# LightingBoard2.net
KiCad netlist of a schematic drawn in EAGLE
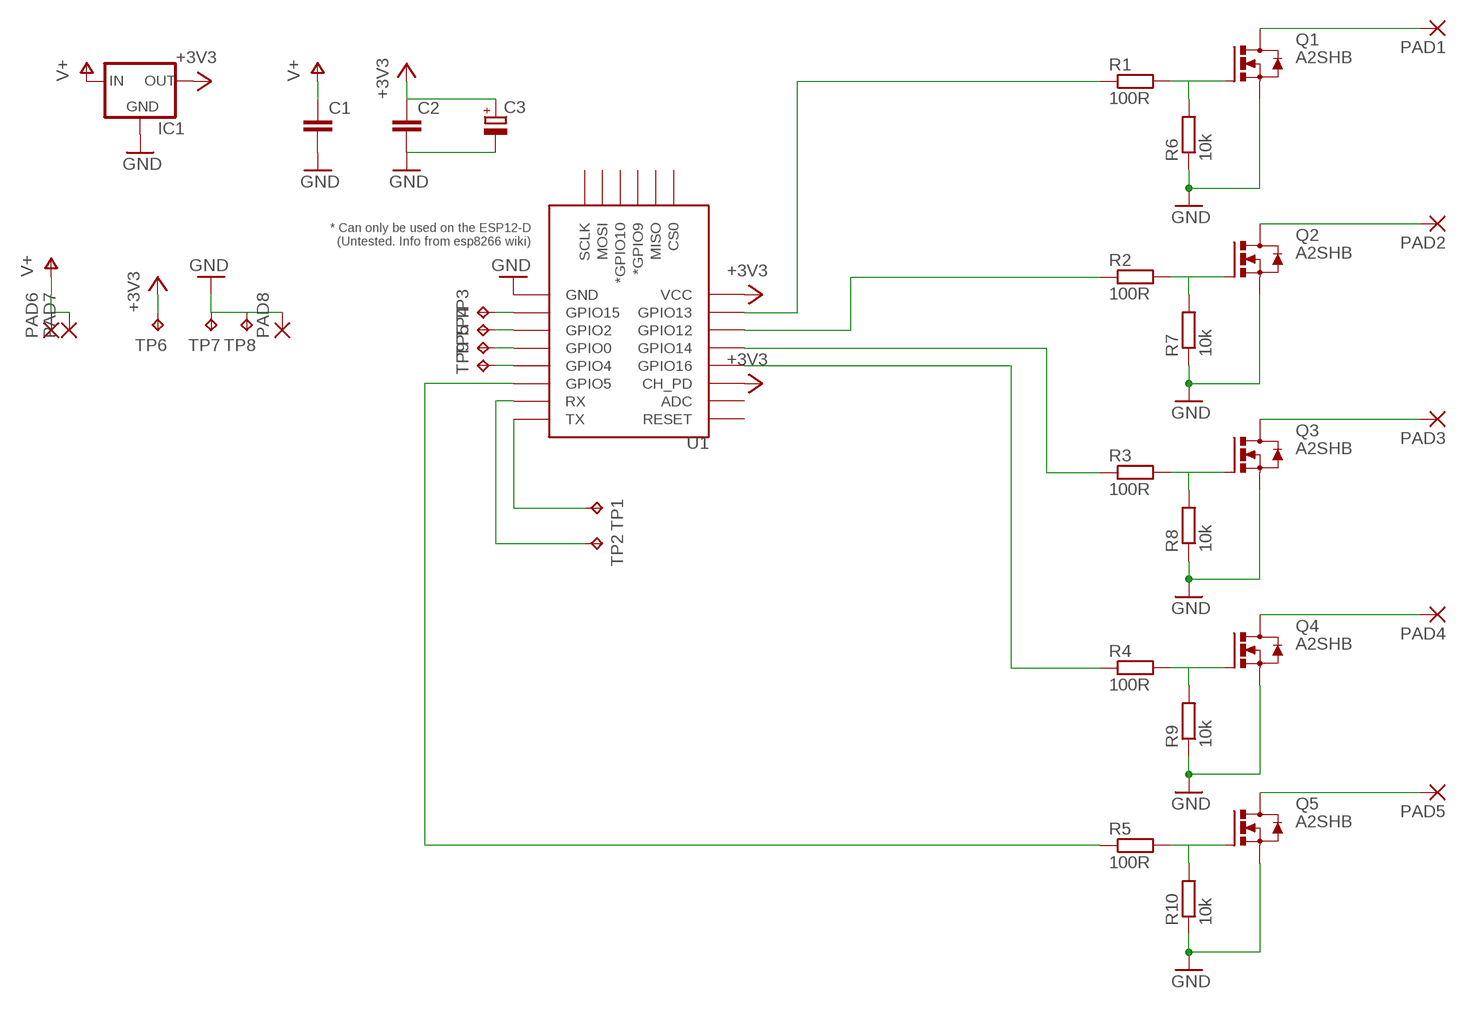
[diagram p0: schematic, sheet 1]

(export (version "E")
  (design (tool "Eeschema 10.0.6"))
  (components
    (comp (ref "C1")
      (value "C-EUC0603")
      (footprint "eagle-import:C0603")
      (libsource (lib "eagle-import") (part "C-EUC0603"))
    )
    (comp (ref "C2")
      (value "C-EUC0603")
      (footprint "eagle-import:C0603")
      (libsource (lib "eagle-import") (part "C-EUC0603"))
    )
    (comp (ref "C3")
      (value "CPOL-EU153CLV-0505")
      (footprint "eagle-import:153CLV-0505")
      (libsource (lib "eagle-import") (part "CPOL-EU153CLV-0505"))
    )
    (comp (ref "IC1")
      (value "LM1117")
      (footprint "eagle-import:SOT223")
      (libsource (lib "eagle-import") (part "LM1117"))
    )
    (comp (ref "PAD1")
      (value "SMD5")
      (footprint "eagle-import:SMD2,54-5,08")
      (libsource (lib "eagle-import") (part "SMD5"))
    )
    (comp (ref "PAD2")
      (value "SMD5")
      (footprint "eagle-import:SMD2,54-5,08")
      (libsource (lib "eagle-import") (part "SMD5"))
    )
    (comp (ref "PAD3")
      (value "SMD5")
      (footprint "eagle-import:SMD2,54-5,08")
      (libsource (lib "eagle-import") (part "SMD5"))
    )
    (comp (ref "PAD4")
      (value "SMD5")
      (footprint "eagle-import:SMD2,54-5,08")
      (libsource (lib "eagle-import") (part "SMD5"))
    )
    (comp (ref "PAD5")
      (value "SMD5")
      (footprint "eagle-import:SMD2,54-5,08")
      (libsource (lib "eagle-import") (part "SMD5"))
    )
    (comp (ref "PAD6")
      (value "SMD5")
      (footprint "eagle-import:SMD2,54-5,08")
      (libsource (lib "eagle-import") (part "SMD5"))
    )
    (comp (ref "PAD7")
      (value "SMD5")
      (footprint "eagle-import:SMD2,54-5,08")
      (libsource (lib "eagle-import") (part "SMD5"))
    )
    (comp (ref "PAD8")
      (value "SMD5")
      (footprint "eagle-import:SMD2,54-5,08")
      (libsource (lib "eagle-import") (part "SMD5"))
    )
    (comp (ref "Q1")
      (value "A2SHB")
      (footprint "eagle-import:SOT23")
      (libsource (lib "eagle-import") (part "MOSFET_N_SOT231"))
    )
    (comp (ref "Q2")
      (value "A2SHB")
      (footprint "eagle-import:SOT23")
      (libsource (lib "eagle-import") (part "MOSFET_N_SOT231"))
    )
    (comp (ref "Q3")
      (value "A2SHB")
      (footprint "eagle-import:SOT23")
      (libsource (lib "eagle-import") (part "MOSFET_N_SOT231"))
    )
    (comp (ref "Q4")
      (value "A2SHB")
      (footprint "eagle-import:SOT23")
      (libsource (lib "eagle-import") (part "MOSFET_N_SOT231"))
    )
    (comp (ref "Q5")
      (value "A2SHB")
      (footprint "eagle-import:SOT23")
      (libsource (lib "eagle-import") (part "MOSFET_N_SOT231"))
    )
    (comp (ref "R1")
      (value "100R")
      (footprint "eagle-import:R0603")
      (libsource (lib "eagle-import") (part "R-EU_R0603"))
    )
    (comp (ref "R2")
      (value "100R")
      (footprint "eagle-import:R0603")
      (libsource (lib "eagle-import") (part "R-EU_R0603"))
    )
    (comp (ref "R3")
      (value "100R")
      (footprint "eagle-import:R0603")
      (libsource (lib "eagle-import") (part "R-EU_R0603"))
    )
    (comp (ref "R4")
      (value "100R")
      (footprint "eagle-import:R0603")
      (libsource (lib "eagle-import") (part "R-EU_R0603"))
    )
    (comp (ref "R5")
      (value "100R")
      (footprint "eagle-import:R0603")
      (libsource (lib "eagle-import") (part "R-EU_R0603"))
    )
    (comp (ref "R6")
      (value "10k")
      (footprint "eagle-import:R0603")
      (libsource (lib "eagle-import") (part "R-EU_R0603"))
    )
    (comp (ref "R7")
      (value "10k")
      (footprint "eagle-import:R0603")
      (libsource (lib "eagle-import") (part "R-EU_R0603"))
    )
    (comp (ref "R8")
      (value "10k")
      (footprint "eagle-import:R0603")
      (libsource (lib "eagle-import") (part "R-EU_R0603"))
    )
    (comp (ref "R9")
      (value "10k")
      (footprint "eagle-import:R0603")
      (libsource (lib "eagle-import") (part "R-EU_R0603"))
    )
    (comp (ref "R10")
      (value "10k")
      (footprint "eagle-import:R0603")
      (libsource (lib "eagle-import") (part "R-EU_R0603"))
    )
    (comp (ref "TP1")
      (value "TPTP18R")
      (footprint "eagle-import:TP18R")
      (libsource (lib "eagle-import") (part "TPTP18R"))
    )
    (comp (ref "TP2")
      (value "TPTP18R")
      (footprint "eagle-import:TP18R")
      (libsource (lib "eagle-import") (part "TPTP18R"))
    )
    (comp (ref "TP3")
      (value "TPTP12SQ")
      (footprint "eagle-import:TP12SQ")
      (libsource (lib "eagle-import") (part "TPTP12SQ"))
    )
    (comp (ref "TP4")
      (value "TPTP12SQ")
      (footprint "eagle-import:TP12SQ")
      (libsource (lib "eagle-import") (part "TPTP12SQ"))
    )
    (comp (ref "TP5")
      (value "TPTP12SQ")
      (footprint "eagle-import:TP12SQ")
      (libsource (lib "eagle-import") (part "TPTP12SQ"))
    )
    (comp (ref "TP6")
      (value "TPTP12SQ")
      (footprint "eagle-import:TP12SQ")
      (libsource (lib "eagle-import") (part "TPTP12SQ"))
    )
    (comp (ref "TP7")
      (value "TPTP12SQ")
      (footprint "eagle-import:TP12SQ")
      (libsource (lib "eagle-import") (part "TPTP12SQ"))
    )
    (comp (ref "TP8")
      (value "TPTP12SQ")
      (footprint "eagle-import:TP12SQ")
      (libsource (lib "eagle-import") (part "TPTP12SQ"))
    )
    (comp (ref "TP9")
      (value "TPTP12SQ")
      (footprint "eagle-import:TP12SQ")
      (libsource (lib "eagle-import") (part "TPTP12SQ"))
    )
    (comp (ref "U1")
      (value "ESP12ESMD")
      (footprint "eagle-import:ESP12E-SMD")
      (libsource (lib "eagle-import") (part "ESP12ESMD"))
    )
  )
  (nets
    (net (code "1") (name "+3V3") (class "Default")
      (node (ref "C2") (pin "1") (pinfunction "1_1") (pintype "passive"))
      (node (ref "C3") (pin "+") (pinfunction "+_+") (pintype "passive"))
      (node (ref "IC1") (pin "2") (pinfunction "OUT_2") (pintype "passive"))
      (node (ref "TP6") (pin "TP") (pinfunction "TP_TP") (pintype "input"))
      (node (ref "U1") (pin "CH_PD") (pinfunction "CH_PD_CH_PD") (pintype "bidirectional"))
      (node (ref "U1") (pin "VCC") (pinfunction "VCC_VCC") (pintype "bidirectional"))
    )
    (net (code "2") (name "GND") (class "Default")
      (node (ref "C1") (pin "2") (pinfunction "2_2") (pintype "passive"))
      (node (ref "C2") (pin "2") (pinfunction "2_2") (pintype "passive"))
      (node (ref "C3") (pin "-") (pinfunction "-_-") (pintype "passive"))
      (node (ref "IC1") (pin "1") (pinfunction "GND_1") (pintype "input"))
      (node (ref "PAD8") (pin "1") (pinfunction "P_1") (pintype "passive"))
      (node (ref "Q1") (pin "2") (pinfunction "S_2") (pintype "passive"))
      (node (ref "Q2") (pin "2") (pinfunction "S_2") (pintype "passive"))
      (node (ref "Q3") (pin "2") (pinfunction "S_2") (pintype "passive"))
      (node (ref "Q4") (pin "2") (pinfunction "S_2") (pintype "passive"))
      (node (ref "Q5") (pin "2") (pinfunction "S_2") (pintype "passive"))
      (node (ref "R10") (pin "1") (pinfunction "1_1") (pintype "passive"))
      (node (ref "R6") (pin "1") (pinfunction "1_1") (pintype "passive"))
      (node (ref "R7") (pin "1") (pinfunction "1_1") (pintype "passive"))
      (node (ref "R8") (pin "1") (pinfunction "1_1") (pintype "passive"))
      (node (ref "R9") (pin "1") (pinfunction "1_1") (pintype "passive"))
      (node (ref "TP7") (pin "TP") (pinfunction "TP_TP") (pintype "input"))
      (node (ref "TP8") (pin "TP") (pinfunction "TP_TP") (pintype "input"))
      (node (ref "U1") (pin "GND") (pinfunction "GND_GND") (pintype "bidirectional"))
    )
    (net (code "3") (name "Net-(PAD1-P)") (class "Default")
      (node (ref "PAD1") (pin "1") (pinfunction "P_1") (pintype "passive"))
      (node (ref "Q1") (pin "3") (pinfunction "D_3") (pintype "passive"))
    )
    (net (code "4") (name "Net-(PAD2-P)") (class "Default")
      (node (ref "PAD2") (pin "1") (pinfunction "P_1") (pintype "passive"))
      (node (ref "Q2") (pin "3") (pinfunction "D_3") (pintype "passive"))
    )
    (net (code "5") (name "Net-(PAD3-P)") (class "Default")
      (node (ref "PAD3") (pin "1") (pinfunction "P_1") (pintype "passive"))
      (node (ref "Q3") (pin "3") (pinfunction "D_3") (pintype "passive"))
    )
    (net (code "6") (name "Net-(PAD4-P)") (class "Default")
      (node (ref "PAD4") (pin "1") (pinfunction "P_1") (pintype "passive"))
      (node (ref "Q4") (pin "3") (pinfunction "D_3") (pintype "passive"))
    )
    (net (code "7") (name "Net-(PAD5-P)") (class "Default")
      (node (ref "PAD5") (pin "1") (pinfunction "P_1") (pintype "passive"))
      (node (ref "Q5") (pin "3") (pinfunction "D_3") (pintype "passive"))
    )
    (net (code "8") (name "Net-(Q1-G)") (class "Default")
      (node (ref "Q1") (pin "1") (pinfunction "G_1") (pintype "passive"))
      (node (ref "R1") (pin "2") (pinfunction "2_2") (pintype "passive"))
      (node (ref "R6") (pin "2") (pinfunction "2_2") (pintype "passive"))
    )
    (net (code "9") (name "Net-(Q2-G)") (class "Default")
      (node (ref "Q2") (pin "1") (pinfunction "G_1") (pintype "passive"))
      (node (ref "R2") (pin "2") (pinfunction "2_2") (pintype "passive"))
      (node (ref "R7") (pin "2") (pinfunction "2_2") (pintype "passive"))
    )
    (net (code "10") (name "Net-(Q3-G)") (class "Default")
      (node (ref "Q3") (pin "1") (pinfunction "G_1") (pintype "passive"))
      (node (ref "R3") (pin "2") (pinfunction "2_2") (pintype "passive"))
      (node (ref "R8") (pin "2") (pinfunction "2_2") (pintype "passive"))
    )
    (net (code "11") (name "Net-(Q4-G)") (class "Default")
      (node (ref "Q4") (pin "1") (pinfunction "G_1") (pintype "passive"))
      (node (ref "R4") (pin "2") (pinfunction "2_2") (pintype "passive"))
      (node (ref "R9") (pin "2") (pinfunction "2_2") (pintype "passive"))
    )
    (net (code "12") (name "Net-(Q5-G)") (class "Default")
      (node (ref "Q5") (pin "1") (pinfunction "G_1") (pintype "passive"))
      (node (ref "R10") (pin "2") (pinfunction "2_2") (pintype "passive"))
      (node (ref "R5") (pin "2") (pinfunction "2_2") (pintype "passive"))
    )
    (net (code "13") (name "Net-(R1-Pad1)") (class "Default")
      (node (ref "R1") (pin "1") (pinfunction "1_1") (pintype "passive"))
      (node (ref "U1") (pin "GPIO13") (pinfunction "GPIO13_GPIO13") (pintype "bidirectional"))
    )
    (net (code "14") (name "Net-(R2-Pad1)") (class "Default")
      (node (ref "R2") (pin "1") (pinfunction "1_1") (pintype "passive"))
      (node (ref "U1") (pin "GPIO12") (pinfunction "GPIO12_GPIO12") (pintype "bidirectional"))
    )
    (net (code "15") (name "Net-(R3-Pad1)") (class "Default")
      (node (ref "R3") (pin "1") (pinfunction "1_1") (pintype "passive"))
      (node (ref "U1") (pin "GPIO14") (pinfunction "GPIO14_GPIO14") (pintype "bidirectional"))
    )
    (net (code "16") (name "Net-(R4-Pad1)") (class "Default")
      (node (ref "R4") (pin "1") (pinfunction "1_1") (pintype "passive"))
      (node (ref "U1") (pin "GPIO16") (pinfunction "GPIO16_GPIO16") (pintype "bidirectional"))
    )
    (net (code "17") (name "Net-(R5-Pad1)") (class "Default")
      (node (ref "R5") (pin "1") (pinfunction "1_1") (pintype "passive"))
      (node (ref "U1") (pin "GPIO5") (pinfunction "GPIO5_GPIO5") (pintype "bidirectional"))
    )
    (net (code "18") (name "Net-(TP3-PadTP)") (class "Default")
      (node (ref "TP3") (pin "TP") (pinfunction "TP_TP") (pintype "input"))
      (node (ref "U1") (pin "GPIO15") (pinfunction "GPIO15_GPIO15") (pintype "bidirectional"))
    )
    (net (code "19") (name "Net-(TP4-PadTP)") (class "Default")
      (node (ref "TP4") (pin "TP") (pinfunction "TP_TP") (pintype "input"))
      (node (ref "U1") (pin "GPIO2") (pinfunction "GPIO2_GPIO2") (pintype "bidirectional"))
    )
    (net (code "20") (name "Net-(TP5-PadTP)") (class "Default")
      (node (ref "TP5") (pin "TP") (pinfunction "TP_TP") (pintype "input"))
      (node (ref "U1") (pin "GPIO0") (pinfunction "GPIO0_GPIO0") (pintype "bidirectional"))
    )
    (net (code "21") (name "Net-(TP9-PadTP)") (class "Default")
      (node (ref "TP9") (pin "TP") (pinfunction "TP_TP") (pintype "input"))
      (node (ref "U1") (pin "GPIO4") (pinfunction "GPIO4_GPIO4") (pintype "bidirectional"))
    )
    (net (code "22") (name "Net-(U1-RX)") (class "Default")
      (node (ref "TP2") (pin "TP") (pinfunction "TP_TP") (pintype "input"))
      (node (ref "U1") (pin "RXD0") (pinfunction "RX_RXD0") (pintype "bidirectional"))
    )
    (net (code "23") (name "Net-(U1-TX)") (class "Default")
      (node (ref "TP1") (pin "TP") (pinfunction "TP_TP") (pintype "input"))
      (node (ref "U1") (pin "TXD0") (pinfunction "TX_TXD0") (pintype "bidirectional"))
    )
    (net (code "24") (name "V+") (class "Default")
      (node (ref "C1") (pin "1") (pinfunction "1_1") (pintype "passive"))
      (node (ref "IC1") (pin "3") (pinfunction "IN_3") (pintype "input"))
      (node (ref "PAD6") (pin "1") (pinfunction "P_1") (pintype "passive"))
      (node (ref "PAD7") (pin "1") (pinfunction "P_1") (pintype "passive"))
    )
    (net (code "25") (name "unconnected-(U1-*GPIO9-PadGPIO9)") (class "Default")
      (node (ref "U1") (pin "GPIO9") (pinfunction "*GPIO9_GPIO9") (pintype "bidirectional"))
    )
    (net (code "26") (name "unconnected-(U1-*GPIO10-PadGPIO10)") (class "Default")
      (node (ref "U1") (pin "GPIO10") (pinfunction "*GPIO10_GPIO10") (pintype "bidirectional"))
    )
    (net (code "27") (name "unconnected-(U1-PadADC)") (class "Default")
      (node (ref "U1") (pin "ADC") (pinfunction "ADC_ADC") (pintype "bidirectional"))
    )
    (net (code "28") (name "unconnected-(U1-PadCS0)") (class "Default")
      (node (ref "U1") (pin "CS0") (pinfunction "CS0_CS0") (pintype "bidirectional"))
    )
    (net (code "29") (name "unconnected-(U1-PadMISO)") (class "Default")
      (node (ref "U1") (pin "MISO") (pinfunction "MISO_MISO") (pintype "bidirectional"))
    )
    (net (code "30") (name "unconnected-(U1-PadMOSI)") (class "Default")
      (node (ref "U1") (pin "MOSI") (pinfunction "MOSI_MOSI") (pintype "bidirectional"))
    )
    (net (code "31") (name "unconnected-(U1-PadRESET)") (class "Default")
      (node (ref "U1") (pin "RESET") (pinfunction "RESET_RESET") (pintype "bidirectional"))
    )
    (net (code "32") (name "unconnected-(U1-PadSCLK)") (class "Default")
      (node (ref "U1") (pin "SCLK") (pinfunction "SCLK_SCLK") (pintype "bidirectional"))
    )
  )
)
